# PCB-Switches.net
KiCad netlist of a schematic drawn in EAGLE
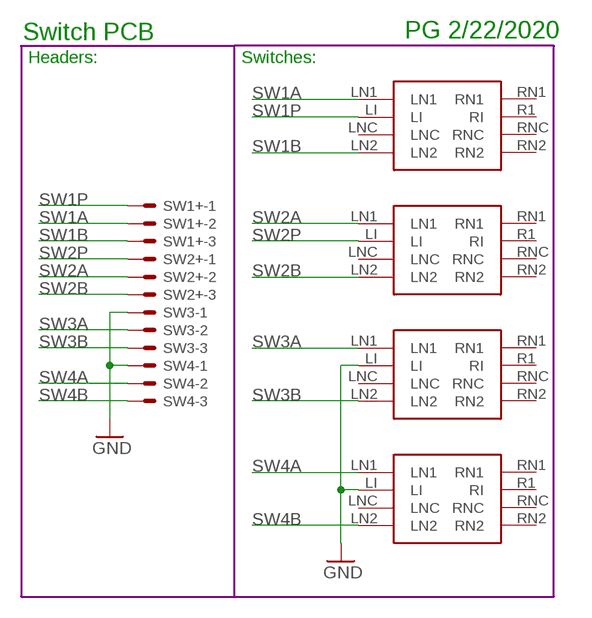
[diagram p0: schematic, sheet 1]

(export (version "E")
  (design (tool "Eeschema 10.0.6"))
  (components
    (comp (ref "SW1+")
      (value "KK-156-3")
      (footprint "eagle-import:KK-156-3")
      (fields (field (name "MF") "MOLEX"))
      (libsource (lib "eagle-import") (part "KK-156-3"))
    )
    (comp (ref "SW2+")
      (value "KK-156-3")
      (footprint "eagle-import:KK-156-3")
      (fields (field (name "MF") "MOLEX"))
      (libsource (lib "eagle-import") (part "KK-156-3"))
    )
    (comp (ref "SW3")
      (value "KK-156-3")
      (footprint "eagle-import:KK-156-3")
      (fields (field (name "MF") "MOLEX"))
      (libsource (lib "eagle-import") (part "KK-156-3"))
    )
    (comp (ref "SW4")
      (value "KK-156-3")
      (footprint "eagle-import:KK-156-3")
      (fields (field (name "MF") "MOLEX"))
      (libsource (lib "eagle-import") (part "KK-156-3"))
    )
    (comp (ref "U$1")
      (value "ARCADESWITCH")
      (footprint "eagle-import:ARCADESWITCH")
      (libsource (lib "eagle-import") (part "ARCADESWITCH"))
    )
    (comp (ref "U$2")
      (value "ARCADESWITCH")
      (footprint "eagle-import:ARCADESWITCH")
      (libsource (lib "eagle-import") (part "ARCADESWITCH"))
    )
    (comp (ref "U$3")
      (value "ARCADESWITCH")
      (footprint "eagle-import:ARCADESWITCH")
      (libsource (lib "eagle-import") (part "ARCADESWITCH"))
    )
    (comp (ref "U$4")
      (value "ARCADESWITCH")
      (footprint "eagle-import:ARCADESWITCH")
      (libsource (lib "eagle-import") (part "ARCADESWITCH"))
    )
  )
  (nets
    (net (code "1") (name "/SW1A") (class "Default")
      (node (ref "SW1+") (pin "2") (pinfunction "S_2") (pintype "passive"))
      (node (ref "U$1") (pin "LN1") (pinfunction "LN1_LN1") (pintype "bidirectional"))
    )
    (net (code "2") (name "/SW1B") (class "Default")
      (node (ref "SW1+") (pin "3") (pinfunction "S_3") (pintype "passive"))
      (node (ref "U$1") (pin "LN2") (pinfunction "LN2_LN2") (pintype "bidirectional"))
    )
    (net (code "3") (name "/SW1P") (class "Default")
      (node (ref "SW1+") (pin "1") (pinfunction "S_1") (pintype "passive"))
      (node (ref "U$1") (pin "LI") (pinfunction "LI_LI") (pintype "bidirectional"))
    )
    (net (code "4") (name "/SW2A") (class "Default")
      (node (ref "SW2+") (pin "2") (pinfunction "S_2") (pintype "passive"))
      (node (ref "U$2") (pin "LN1") (pinfunction "LN1_LN1") (pintype "bidirectional"))
    )
    (net (code "5") (name "/SW2B") (class "Default")
      (node (ref "SW2+") (pin "3") (pinfunction "S_3") (pintype "passive"))
      (node (ref "U$2") (pin "LN2") (pinfunction "LN2_LN2") (pintype "bidirectional"))
    )
    (net (code "6") (name "/SW2P") (class "Default")
      (node (ref "SW2+") (pin "1") (pinfunction "S_1") (pintype "passive"))
      (node (ref "U$2") (pin "LI") (pinfunction "LI_LI") (pintype "bidirectional"))
    )
    (net (code "7") (name "/SW3A") (class "Default")
      (node (ref "SW3") (pin "2") (pinfunction "S_2") (pintype "passive"))
      (node (ref "U$3") (pin "LN1") (pinfunction "LN1_LN1") (pintype "bidirectional"))
    )
    (net (code "8") (name "/SW3B") (class "Default")
      (node (ref "SW3") (pin "3") (pinfunction "S_3") (pintype "passive"))
      (node (ref "U$3") (pin "LN2") (pinfunction "LN2_LN2") (pintype "bidirectional"))
    )
    (net (code "9") (name "/SW4A") (class "Default")
      (node (ref "SW4") (pin "2") (pinfunction "S_2") (pintype "passive"))
      (node (ref "U$4") (pin "LN1") (pinfunction "LN1_LN1") (pintype "bidirectional"))
    )
    (net (code "10") (name "/SW4B") (class "Default")
      (node (ref "SW4") (pin "3") (pinfunction "S_3") (pintype "passive"))
      (node (ref "U$4") (pin "LN2") (pinfunction "LN2_LN2") (pintype "bidirectional"))
    )
    (net (code "11") (name "GND") (class "Default")
      (node (ref "SW3") (pin "1") (pinfunction "S_1") (pintype "passive"))
      (node (ref "SW4") (pin "1") (pinfunction "S_1") (pintype "passive"))
      (node (ref "U$3") (pin "LI") (pinfunction "LI_LI") (pintype "bidirectional"))
      (node (ref "U$4") (pin "LI") (pinfunction "LI_LI") (pintype "bidirectional"))
    )
    (net (code "12") (name "unconnected-(U$1-PadLNC)") (class "Default")
      (node (ref "U$1") (pin "LNC") (pinfunction "LNC_LNC") (pintype "bidirectional"))
    )
    (net (code "13") (name "unconnected-(U$1-PadRN1)") (class "Default")
      (node (ref "U$1") (pin "RN1") (pinfunction "RN1_RN1") (pintype "bidirectional"))
    )
    (net (code "14") (name "unconnected-(U$1-PadRN2)") (class "Default")
      (node (ref "U$1") (pin "RN2") (pinfunction "RN2_RN2") (pintype "bidirectional"))
    )
    (net (code "15") (name "unconnected-(U$1-PadRNC)") (class "Default")
      (node (ref "U$1") (pin "RNC") (pinfunction "RNC_RNC") (pintype "bidirectional"))
    )
    (net (code "16") (name "unconnected-(U$1-RI-PadR1)") (class "Default")
      (node (ref "U$1") (pin "R1") (pinfunction "RI_R1") (pintype "bidirectional"))
    )
    (net (code "17") (name "unconnected-(U$2-PadLNC)") (class "Default")
      (node (ref "U$2") (pin "LNC") (pinfunction "LNC_LNC") (pintype "bidirectional"))
    )
    (net (code "18") (name "unconnected-(U$2-PadRN1)") (class "Default")
      (node (ref "U$2") (pin "RN1") (pinfunction "RN1_RN1") (pintype "bidirectional"))
    )
    (net (code "19") (name "unconnected-(U$2-PadRN2)") (class "Default")
      (node (ref "U$2") (pin "RN2") (pinfunction "RN2_RN2") (pintype "bidirectional"))
    )
    (net (code "20") (name "unconnected-(U$2-PadRNC)") (class "Default")
      (node (ref "U$2") (pin "RNC") (pinfunction "RNC_RNC") (pintype "bidirectional"))
    )
    (net (code "21") (name "unconnected-(U$2-RI-PadR1)") (class "Default")
      (node (ref "U$2") (pin "R1") (pinfunction "RI_R1") (pintype "bidirectional"))
    )
    (net (code "22") (name "unconnected-(U$3-PadLNC)") (class "Default")
      (node (ref "U$3") (pin "LNC") (pinfunction "LNC_LNC") (pintype "bidirectional"))
    )
    (net (code "23") (name "unconnected-(U$3-PadRN1)") (class "Default")
      (node (ref "U$3") (pin "RN1") (pinfunction "RN1_RN1") (pintype "bidirectional"))
    )
    (net (code "24") (name "unconnected-(U$3-PadRN2)") (class "Default")
      (node (ref "U$3") (pin "RN2") (pinfunction "RN2_RN2") (pintype "bidirectional"))
    )
    (net (code "25") (name "unconnected-(U$3-PadRNC)") (class "Default")
      (node (ref "U$3") (pin "RNC") (pinfunction "RNC_RNC") (pintype "bidirectional"))
    )
    (net (code "26") (name "unconnected-(U$3-RI-PadR1)") (class "Default")
      (node (ref "U$3") (pin "R1") (pinfunction "RI_R1") (pintype "bidirectional"))
    )
    (net (code "27") (name "unconnected-(U$4-PadLNC)") (class "Default")
      (node (ref "U$4") (pin "LNC") (pinfunction "LNC_LNC") (pintype "bidirectional"))
    )
    (net (code "28") (name "unconnected-(U$4-PadRN1)") (class "Default")
      (node (ref "U$4") (pin "RN1") (pinfunction "RN1_RN1") (pintype "bidirectional"))
    )
    (net (code "29") (name "unconnected-(U$4-PadRN2)") (class "Default")
      (node (ref "U$4") (pin "RN2") (pinfunction "RN2_RN2") (pintype "bidirectional"))
    )
    (net (code "30") (name "unconnected-(U$4-PadRNC)") (class "Default")
      (node (ref "U$4") (pin "RNC") (pinfunction "RNC_RNC") (pintype "bidirectional"))
    )
    (net (code "31") (name "unconnected-(U$4-RI-PadR1)") (class "Default")
      (node (ref "U$4") (pin "R1") (pinfunction "RI_R1") (pintype "bidirectional"))
    )
  )
)
